# ESP32-S2.net
KiCad netlist of a schematic drawn in Altium Designer
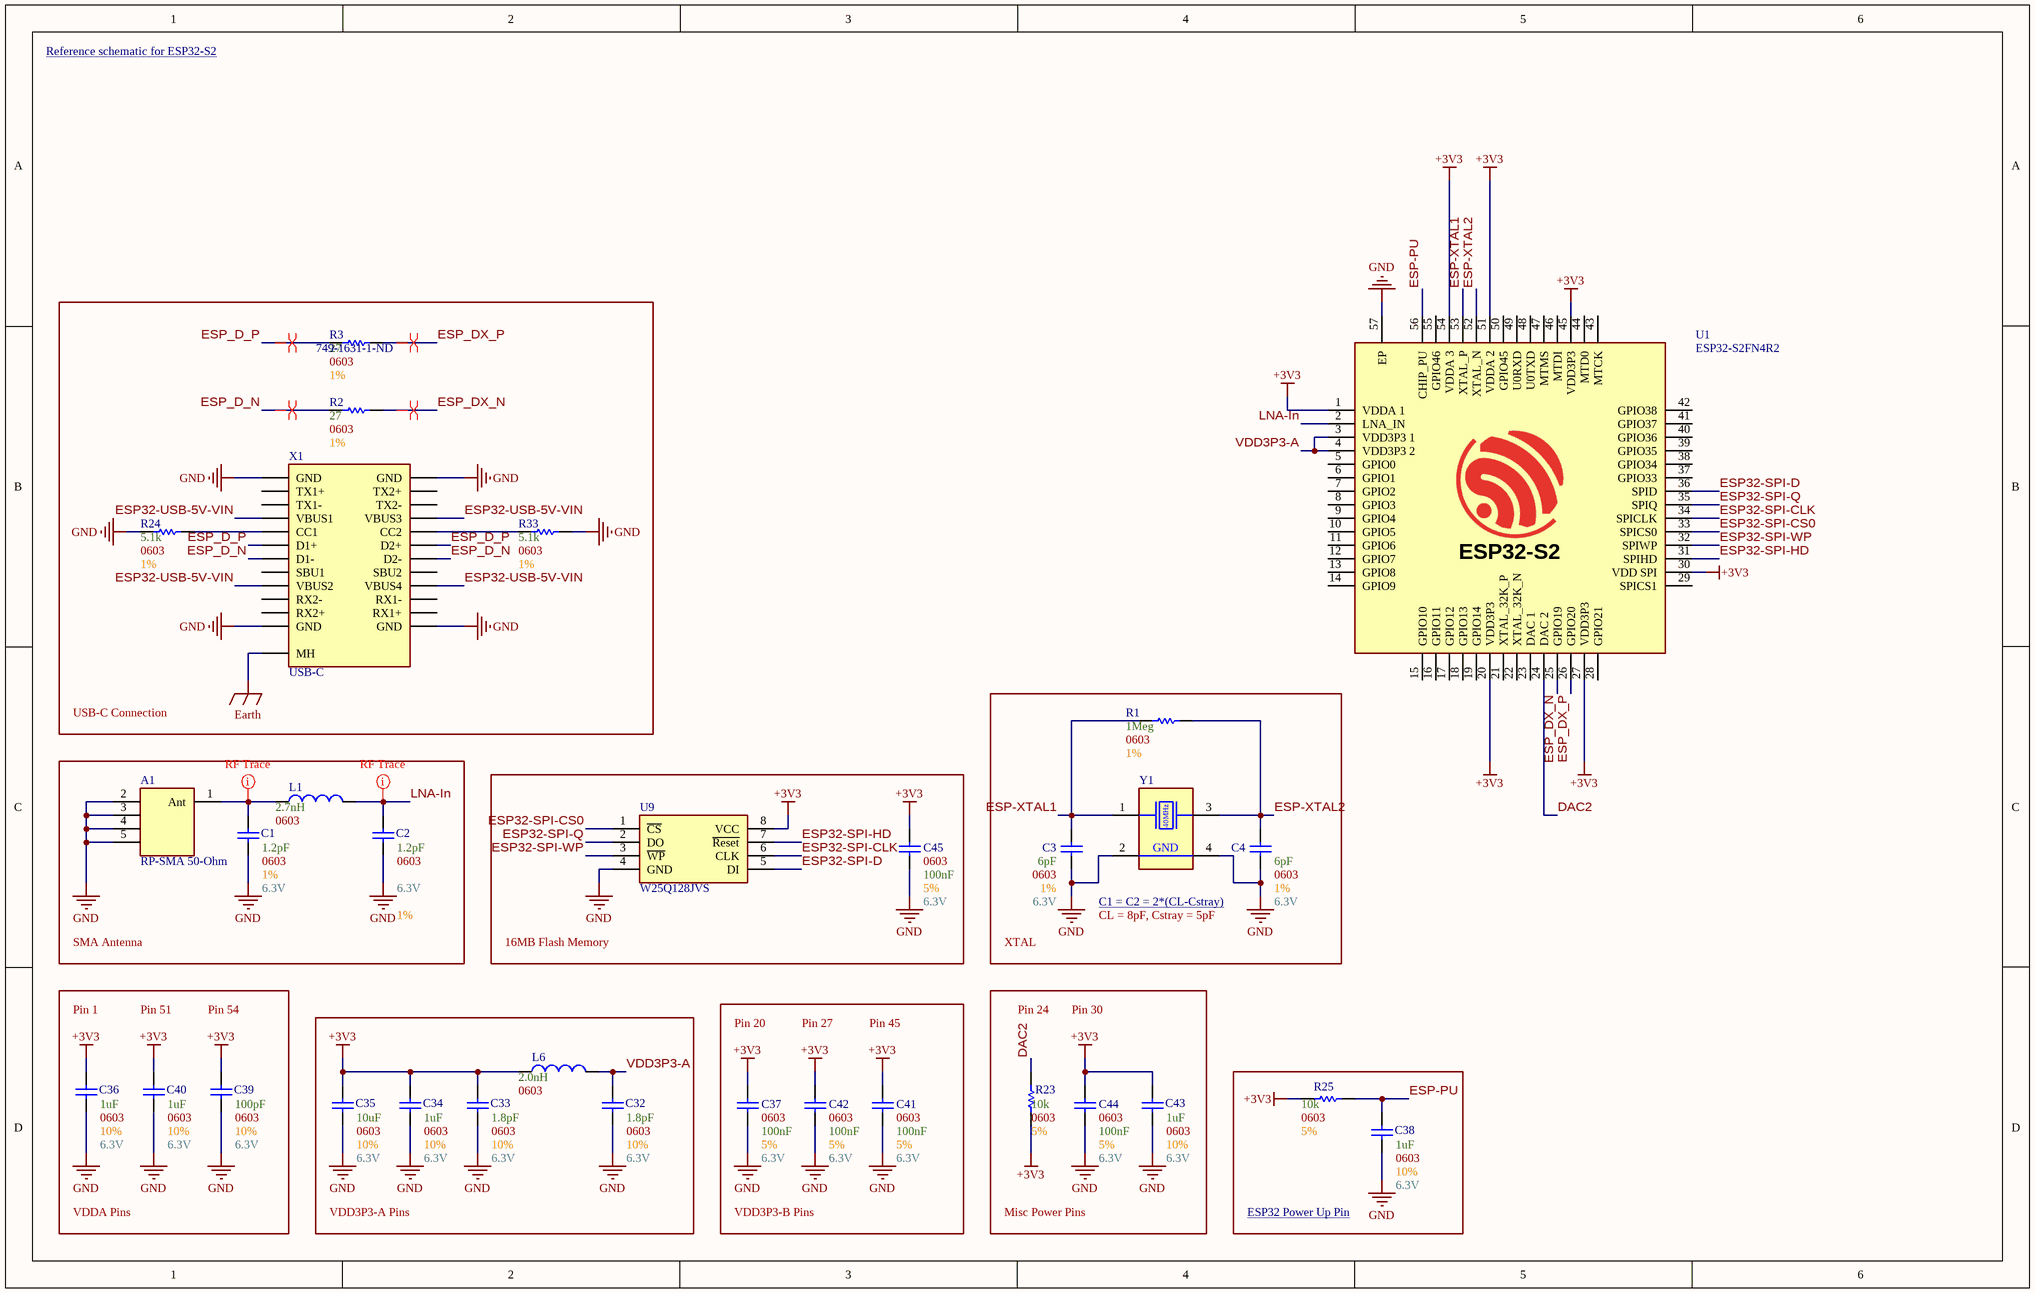
[diagram p0: ESP32-S2.SchDoc]

(export (version "E")
  (design (tool "Eeschema 10.0.6"))
  (components
    (comp (ref "A1")
      (value "RP-SMA 50-Ohm")
      (footprint "[SMA] RP-SMA 90deg Jack")
      (description "PCB.RPSMAFRA.HT")
      (libsource (lib "RADM Connectors") (part "[SMA] RP-SMA 90deg Jack"))
    )
    (comp (ref "C1")
      (value "SMD Nonpolarized")
      (footprint "[Cap] SMD 0603")
      (fields
        (field (name "VOLTAGE") "6.3V")
        (field (name "TOLERANCE") "1%")
        (field (name "SIZE PACKAGE") "0603")
        (field (name "CAPACITANCE") "1.2pF")
      )
      (libsource (lib "RADM Components") (part "[Cap] SMD Nonpolarized"))
    )
    (comp (ref "C2")
      (value "SMD Nonpolarized")
      (footprint "[Cap] SMD 0603")
      (fields
        (field (name "VOLTAGE") "6.3V")
        (field (name "TOLERANCE") "1%")
        (field (name "SIZE PACKAGE") "0603")
        (field (name "CAPACITANCE") "1.2pF")
      )
      (libsource (lib "RADM Components") (part "[Cap] SMD Nonpolarized"))
    )
    (comp (ref "C3")
      (value "SMD Nonpolarized")
      (footprint "[Cap] SMD 0603")
      (fields
        (field (name "VOLTAGE") "6.3V")
        (field (name "TOLERANCE") "1%")
        (field (name "SIZE PACKAGE") "0603")
        (field (name "CAPACITANCE") "6pF")
      )
      (libsource (lib "RADM Components") (part "[Cap] SMD Nonpolarized"))
    )
    (comp (ref "C4")
      (value "SMD Nonpolarized")
      (footprint "[Cap] SMD 0603")
      (fields
        (field (name "VOLTAGE") "6.3V")
        (field (name "TOLERANCE") "1%")
        (field (name "SIZE PACKAGE") "0603")
        (field (name "CAPACITANCE") "6pF")
      )
      (libsource (lib "RADM Components") (part "[Cap] SMD Nonpolarized"))
    )
    (comp (ref "C32")
      (value "SMD Nonpolarized")
      (footprint "[Cap] SMD 0603")
      (fields
        (field (name "VOLTAGE") "6.3V")
        (field (name "TOLERANCE") "10%")
        (field (name "SIZE PACKAGE") "0603")
        (field (name "CAPACITANCE") "1.8pF")
      )
      (libsource (lib "RADM Components") (part "[Cap] SMD Nonpolarized"))
    )
    (comp (ref "C33")
      (value "SMD Nonpolarized")
      (footprint "[Cap] SMD 0603")
      (fields
        (field (name "VOLTAGE") "6.3V")
        (field (name "TOLERANCE") "10%")
        (field (name "SIZE PACKAGE") "0603")
        (field (name "CAPACITANCE") "1.8pF")
      )
      (libsource (lib "RADM Components") (part "[Cap] SMD Nonpolarized"))
    )
    (comp (ref "C34")
      (value "SMD Nonpolarized")
      (footprint "[Cap] SMD 0603")
      (fields
        (field (name "VOLTAGE") "6.3V")
        (field (name "TOLERANCE") "10%")
        (field (name "SIZE PACKAGE") "0603")
        (field (name "CAPACITANCE") "1uF")
      )
      (libsource (lib "RADM Components") (part "[Cap] SMD Nonpolarized"))
    )
    (comp (ref "C35")
      (value "SMD Nonpolarized")
      (footprint "[Cap] SMD 0603")
      (fields
        (field (name "VOLTAGE") "6.3V")
        (field (name "TOLERANCE") "10%")
        (field (name "SIZE PACKAGE") "0603")
        (field (name "CAPACITANCE") "10uF")
      )
      (libsource (lib "RADM Components") (part "[Cap] SMD Nonpolarized"))
    )
    (comp (ref "C36")
      (value "SMD Nonpolarized")
      (footprint "[Cap] SMD 0603")
      (fields
        (field (name "VOLTAGE") "6.3V")
        (field (name "TOLERANCE") "10%")
        (field (name "SIZE PACKAGE") "0603")
        (field (name "CAPACITANCE") "1uF")
      )
      (libsource (lib "RADM Components") (part "[Cap] SMD Nonpolarized"))
    )
    (comp (ref "C37")
      (value "[Cap] SMD Nonpolarized")
      (footprint "[Cap] SMD 0603")
      (fields
        (field (name "SIZE PACKAGE") "0603")
        (field (name "CAPACITANCE") "100nF")
        (field (name "VOLTAGE") "6.3V")
        (field (name "TOLERANCE") "5%")
      )
      (libsource (lib "RADM Components") (part "[Cap] SMD Nonpolarized"))
    )
    (comp (ref "C38")
      (value "SMD Nonpolarized")
      (footprint "[Cap] SMD 0603")
      (fields
        (field (name "VOLTAGE") "6.3V")
        (field (name "TOLERANCE") "10%")
        (field (name "SIZE PACKAGE") "0603")
        (field (name "CAPACITANCE") "1uF")
      )
      (libsource (lib "RADM Components") (part "[Cap] SMD Nonpolarized"))
    )
    (comp (ref "C39")
      (value "SMD Nonpolarized")
      (footprint "[Cap] SMD 0603")
      (fields
        (field (name "VOLTAGE") "6.3V")
        (field (name "TOLERANCE") "10%")
        (field (name "SIZE PACKAGE") "0603")
        (field (name "CAPACITANCE") "100pF")
      )
      (libsource (lib "RADM Components") (part "[Cap] SMD Nonpolarized"))
    )
    (comp (ref "C40")
      (value "SMD Nonpolarized")
      (footprint "[Cap] SMD 0603")
      (fields
        (field (name "VOLTAGE") "6.3V")
        (field (name "TOLERANCE") "10%")
        (field (name "SIZE PACKAGE") "0603")
        (field (name "CAPACITANCE") "1uF")
      )
      (libsource (lib "RADM Components") (part "[Cap] SMD Nonpolarized"))
    )
    (comp (ref "C41")
      (value "[Cap] SMD Nonpolarized")
      (footprint "[Cap] SMD 0603")
      (fields
        (field (name "SIZE PACKAGE") "0603")
        (field (name "CAPACITANCE") "100nF")
        (field (name "VOLTAGE") "6.3V")
        (field (name "TOLERANCE") "5%")
      )
      (libsource (lib "RADM Components") (part "[Cap] SMD Nonpolarized"))
    )
    (comp (ref "C42")
      (value "[Cap] SMD Nonpolarized")
      (footprint "[Cap] SMD 0603")
      (fields
        (field (name "SIZE PACKAGE") "0603")
        (field (name "CAPACITANCE") "100nF")
        (field (name "VOLTAGE") "6.3V")
        (field (name "TOLERANCE") "5%")
      )
      (libsource (lib "RADM Components") (part "[Cap] SMD Nonpolarized"))
    )
    (comp (ref "C43")
      (value "SMD Nonpolarized")
      (footprint "[Cap] SMD 0603")
      (fields
        (field (name "VOLTAGE") "6.3V")
        (field (name "TOLERANCE") "10%")
        (field (name "SIZE PACKAGE") "0603")
        (field (name "CAPACITANCE") "1uF")
      )
      (libsource (lib "RADM Components") (part "[Cap] SMD Nonpolarized"))
    )
    (comp (ref "C44")
      (value "[Cap] SMD Nonpolarized")
      (footprint "[Cap] SMD 0603")
      (fields
        (field (name "SIZE PACKAGE") "0603")
        (field (name "CAPACITANCE") "100nF")
        (field (name "VOLTAGE") "6.3V")
        (field (name "TOLERANCE") "5%")
      )
      (libsource (lib "RADM Components") (part "[Cap] SMD Nonpolarized"))
    )
    (comp (ref "C45")
      (value "[Cap] SMD Nonpolarized")
      (footprint "[Cap] SMD 0603")
      (fields
        (field (name "SIZE PACKAGE") "0603")
        (field (name "CAPACITANCE") "100nF")
        (field (name "VOLTAGE") "6.3V")
        (field (name "TOLERANCE") "5%")
      )
      (libsource (lib "RADM Components") (part "[Cap] SMD Nonpolarized"))
    )
    (comp (ref "L1")
      (value "SMD Inductor")
      (footprint "[Inductor] SMD 0603")
      (fields (field (name "SIZE PACKAGE") "0603") (field (name "INDUCTANCE") "2.7nH"))
      (libsource (lib "RADM Components") (part "[Inductor] SMD Inductor"))
    )
    (comp (ref "L6")
      (value "SMD Inductor")
      (footprint "[Inductor] SMD 0603")
      (fields (field (name "SIZE PACKAGE") "0603") (field (name "INDUCTANCE") "2.0nH"))
      (libsource (lib "RADM Components") (part "[Inductor] SMD Inductor"))
    )
    (comp (ref "R1")
      (value "[Res] SMD Resistor")
      (footprint "[Res] SMD 0603")
      (description "Generic")
      (fields
        (field (name "TOLERANCE") "1%")
        (field (name "RESISTANCE") "1Meg")
        (field (name "SIZE PACKAGE") "0603")
      )
      (libsource (lib "RADM Components") (part "[Res] SMD Resistor"))
    )
    (comp (ref "R2")
      (value "[Res] SMD Resistor")
      (footprint "[Res] SMD 0603")
      (description "Generic")
      (fields
        (field (name "TOLERANCE") "1%")
        (field (name "RESISTANCE") "27")
        (field (name "SIZE PACKAGE") "0603")
      )
      (libsource (lib "RADM Components") (part "[Res] SMD Resistor"))
    )
    (comp (ref "R3")
      (value "[Res] SMD Resistor")
      (footprint "[Res] SMD 0603")
      (description "Generic")
      (fields
        (field (name "TOLERANCE") "1%")
        (field (name "RESISTANCE") "27")
        (field (name "SIZE PACKAGE") "0603")
        (field (name "SUPPLIER PART NUMBER 1") "749-1631-1-ND")
      )
      (libsource (lib "RADM Components") (part "[Res] SMD Resistor"))
    )
    (comp (ref "R23")
      (value "[Res] SMD Resistor")
      (footprint "[Res] SMD 0603")
      (description "Generic")
      (fields
        (field (name "TOLERANCE") "5%")
        (field (name "RESISTANCE") "10k")
        (field (name "SIZE PACKAGE") "0603")
      )
      (libsource (lib "RADM Components") (part "[Res] SMD Resistor"))
    )
    (comp (ref "R24")
      (value "[Res] SMD Resistor")
      (footprint "[Res] SMD 0603")
      (description "Generic")
      (fields
        (field (name "TOLERANCE") "1%")
        (field (name "RESISTANCE") "5.1k")
        (field (name "SIZE PACKAGE") "0603")
      )
      (libsource (lib "RADM Components") (part "[Res] SMD Resistor"))
    )
    (comp (ref "R25")
      (value "[Res] SMD Resistor")
      (footprint "[Res] SMD 0603")
      (description "Generic")
      (fields
        (field (name "TOLERANCE") "5%")
        (field (name "RESISTANCE") "10k")
        (field (name "SIZE PACKAGE") "0603")
      )
      (libsource (lib "RADM Components") (part "[Res] SMD Resistor"))
    )
    (comp (ref "R33")
      (value "[Res] SMD Resistor")
      (footprint "[Res] SMD 0603")
      (description "Generic")
      (fields
        (field (name "TOLERANCE") "1%")
        (field (name "RESISTANCE") "5.1k")
        (field (name "SIZE PACKAGE") "0603")
      )
      (libsource (lib "RADM Components") (part "[Res] SMD Resistor"))
    )
    (comp (ref "U1")
      (value "ESP32-S2FN4R2")
      (footprint "[MCU] ESP32-S2")
      (libsource (lib "RADM Components") (part "[MCU] ESP32-S2"))
    )
    (comp (ref "U9")
      (value "W25Q128JVS")
      (footprint "[Mem] 16Mb Flash Memory")
      (description "W25Q128JVSIQ TR")
      (libsource (lib "RADM Components") (part "[Mem] 16Mb Flash Memory"))
    )
    (comp (ref "X1")
      (value "USB-C")
      (footprint "[Port] USB-C")
      (libsource (lib "RADM Connectors") (part "[Port] USB Type-C"))
    )
    (comp (ref "Y1")
      (value "40MHz Crystal")
      (footprint "[XTAL] SMD 40MHz")
      (description "CX2016DB40000D0FLJCC")
      (libsource (lib "RADM Components") (part "[XTAL] SMD 40MHz"))
    )
  )
  (nets
    (net (code "1") (name "+3V3") (class "Default")
      (node (ref "C33") (pin "2") (pinfunction "2_2") (pintype "passive"))
      (node (ref "C34") (pin "2") (pinfunction "2_2") (pintype "passive"))
      (node (ref "C35") (pin "2") (pinfunction "2_2") (pintype "passive"))
      (node (ref "C36") (pin "2") (pinfunction "2_2") (pintype "passive"))
      (node (ref "C37") (pin "2") (pinfunction "2_2") (pintype "passive"))
      (node (ref "C39") (pin "2") (pinfunction "2_2") (pintype "passive"))
      (node (ref "C40") (pin "2") (pinfunction "2_2") (pintype "passive"))
      (node (ref "C41") (pin "2") (pinfunction "2_2") (pintype "passive"))
      (node (ref "C42") (pin "2") (pinfunction "2_2") (pintype "passive"))
      (node (ref "C43") (pin "2") (pinfunction "2_2") (pintype "passive"))
      (node (ref "C44") (pin "2") (pinfunction "2_2") (pintype "passive"))
      (node (ref "C45") (pin "2") (pinfunction "2_2") (pintype "passive"))
      (node (ref "L6") (pin "1") (pinfunction "1_1") (pintype "passive"))
      (node (ref "R23") (pin "1") (pinfunction "1_1") (pintype "passive"))
      (node (ref "R25") (pin "1") (pinfunction "1_1") (pintype "passive"))
      (node (ref "U1") (pin "1") (pinfunction "VDDA_1_1") (pintype "passive"))
      (node (ref "U1") (pin "20") (pinfunction "VDD3P3_20") (pintype "passive"))
      (node (ref "U1") (pin "27") (pinfunction "VDD3P3_27") (pintype "passive"))
      (node (ref "U1") (pin "30") (pinfunction "VDD_SPI_30") (pintype "passive"))
      (node (ref "U1") (pin "45") (pinfunction "VDD3P3_45") (pintype "passive"))
      (node (ref "U1") (pin "51") (pinfunction "VDDA_2_51") (pintype "passive"))
      (node (ref "U1") (pin "54") (pinfunction "VDDA_3_54") (pintype "passive"))
      (node (ref "U9") (pin "8") (pinfunction "VCC_8") (pintype "passive"))
    )
    (net (code "2") (name "/DAC2") (class "Default")
      (node (ref "R23") (pin "2") (pinfunction "2_2") (pintype "passive"))
      (node (ref "U1") (pin "24") (pinfunction "DAC_2_24") (pintype "passive"))
    )
    (net (code "3") (name "/ESP-PU") (class "Default")
      (node (ref "C38") (pin "2") (pinfunction "2_2") (pintype "passive"))
      (node (ref "R25") (pin "2") (pinfunction "2_2") (pintype "passive"))
      (node (ref "U1") (pin "56") (pinfunction "CHIP_PU_56") (pintype "passive"))
    )
    (net (code "4") (name "/ESP-XTAL1") (class "Default")
      (node (ref "C3") (pin "2") (pinfunction "2_2") (pintype "passive"))
      (node (ref "R1") (pin "2") (pinfunction "2_2") (pintype "passive"))
      (node (ref "U1") (pin "53") (pinfunction "XTAL_P_53") (pintype "passive"))
      (node (ref "Y1") (pin "1") (pinfunction "XTAL1_1") (pintype "power_in"))
    )
    (net (code "5") (name "/ESP-XTAL2") (class "Default")
      (node (ref "C4") (pin "2") (pinfunction "2_2") (pintype "passive"))
      (node (ref "R1") (pin "1") (pinfunction "1_1") (pintype "passive"))
      (node (ref "U1") (pin "52") (pinfunction "XTAL_N_52") (pintype "passive"))
      (node (ref "Y1") (pin "3") (pinfunction "XTAL2_3") (pintype "power_in"))
    )
    (net (code "6") (name "/ESP32-SPI-CLK") (class "Default")
      (node (ref "U1") (pin "34") (pinfunction "SPICLK_34") (pintype "passive"))
      (node (ref "U9") (pin "6") (pinfunction "CLK_6") (pintype "passive"))
    )
    (net (code "7") (name "/ESP32-SPI-CS0") (class "Default")
      (node (ref "U1") (pin "33") (pinfunction "SPICS0_33") (pintype "passive"))
      (node (ref "U9") (pin "1") (pinfunction "~{CS}_1") (pintype "passive"))
    )
    (net (code "8") (name "/ESP32-SPI-D") (class "Default")
      (node (ref "U1") (pin "36") (pinfunction "SPID_36") (pintype "passive"))
      (node (ref "U9") (pin "5") (pinfunction "DI_5") (pintype "passive"))
    )
    (net (code "9") (name "/ESP32-SPI-HD") (class "Default")
      (node (ref "U1") (pin "31") (pinfunction "SPIHD_31") (pintype "passive"))
      (node (ref "U9") (pin "7") (pinfunction "~{Reset}_7") (pintype "passive"))
    )
    (net (code "10") (name "/ESP32-SPI-Q") (class "Default")
      (node (ref "U1") (pin "35") (pinfunction "SPIQ_35") (pintype "passive"))
      (node (ref "U9") (pin "2") (pinfunction "DO_2") (pintype "passive"))
    )
    (net (code "11") (name "/ESP32-SPI-WP") (class "Default")
      (node (ref "U1") (pin "32") (pinfunction "SPIWP_32") (pintype "passive"))
      (node (ref "U9") (pin "3") (pinfunction "~{WP}_3") (pintype "passive"))
    )
    (net (code "12") (name "/ESP32-USB-5V-VIN") (class "Default")
      (node (ref "X1") (pin "A4") (pinfunction "VBUS1_A4") (pintype "passive"))
      (node (ref "X1") (pin "A9") (pinfunction "VBUS2_A9") (pintype "passive"))
      (node (ref "X1") (pin "B4") (pinfunction "VBUS3_B4") (pintype "passive"))
      (node (ref "X1") (pin "B9") (pinfunction "VBUS4_B9") (pintype "passive"))
    )
    (net (code "13") (name "/ESP_DX_N") (class "Default")
      (node (ref "R2") (pin "2") (pinfunction "2_2") (pintype "passive"))
      (node (ref "U1") (pin "25") (pinfunction "GPIO19_25") (pintype "passive"))
    )
    (net (code "14") (name "/ESP_DX_P") (class "Default")
      (node (ref "R3") (pin "2") (pinfunction "2_2") (pintype "passive"))
      (node (ref "U1") (pin "26") (pinfunction "GPIO20_26") (pintype "passive"))
    )
    (net (code "15") (name "/ESP_D_N") (class "Default")
      (node (ref "R2") (pin "1") (pinfunction "1_1") (pintype "passive"))
      (node (ref "X1") (pin "A7") (pinfunction "D1-_A7") (pintype "passive"))
      (node (ref "X1") (pin "B7") (pinfunction "D2-_B7") (pintype "passive"))
    )
    (net (code "16") (name "/ESP_D_P") (class "Default")
      (node (ref "R3") (pin "1") (pinfunction "1_1") (pintype "passive"))
      (node (ref "X1") (pin "A6") (pinfunction "D1+_A6") (pintype "passive"))
      (node (ref "X1") (pin "B6") (pinfunction "D2+_B6") (pintype "passive"))
    )
    (net (code "17") (name "/LNA-In") (class "Default")
      (node (ref "C2") (pin "2") (pinfunction "2_2") (pintype "passive"))
      (node (ref "L1") (pin "2") (pinfunction "2_2") (pintype "passive"))
      (node (ref "U1") (pin "2") (pinfunction "LNA_IN_2") (pintype "passive"))
    )
    (net (code "18") (name "/VDD3P3-A") (class "Default")
      (node (ref "C32") (pin "2") (pinfunction "2_2") (pintype "passive"))
      (node (ref "L6") (pin "2") (pinfunction "2_2") (pintype "passive"))
      (node (ref "U1") (pin "3") (pinfunction "VDD3P3_1_3") (pintype "passive"))
      (node (ref "U1") (pin "4") (pinfunction "VDD3P3_2_4") (pintype "passive"))
    )
    (net (code "19") (name "Earth") (class "Default")
      (node (ref "X1") (pin "MH") (pinfunction "MH_MH") (pintype "passive"))
    )
    (net (code "20") (name "GND") (class "Default")
      (node (ref "A1") (pin "2") (pinfunction "2_2") (pintype "passive"))
      (node (ref "A1") (pin "3") (pinfunction "3_3") (pintype "passive"))
      (node (ref "A1") (pin "4") (pinfunction "4_4") (pintype "passive"))
      (node (ref "A1") (pin "5") (pinfunction "5_5") (pintype "passive"))
      (node (ref "C1") (pin "1") (pinfunction "1_1") (pintype "passive"))
      (node (ref "C2") (pin "1") (pinfunction "1_1") (pintype "passive"))
      (node (ref "C3") (pin "1") (pinfunction "1_1") (pintype "passive"))
      (node (ref "C32") (pin "1") (pinfunction "1_1") (pintype "passive"))
      (node (ref "C33") (pin "1") (pinfunction "1_1") (pintype "passive"))
      (node (ref "C34") (pin "1") (pinfunction "1_1") (pintype "passive"))
      (node (ref "C35") (pin "1") (pinfunction "1_1") (pintype "passive"))
      (node (ref "C36") (pin "1") (pinfunction "1_1") (pintype "passive"))
      (node (ref "C37") (pin "1") (pinfunction "1_1") (pintype "passive"))
      (node (ref "C38") (pin "1") (pinfunction "1_1") (pintype "passive"))
      (node (ref "C39") (pin "1") (pinfunction "1_1") (pintype "passive"))
      (node (ref "C4") (pin "1") (pinfunction "1_1") (pintype "passive"))
      (node (ref "C40") (pin "1") (pinfunction "1_1") (pintype "passive"))
      (node (ref "C41") (pin "1") (pinfunction "1_1") (pintype "passive"))
      (node (ref "C42") (pin "1") (pinfunction "1_1") (pintype "passive"))
      (node (ref "C43") (pin "1") (pinfunction "1_1") (pintype "passive"))
      (node (ref "C44") (pin "1") (pinfunction "1_1") (pintype "passive"))
      (node (ref "C45") (pin "1") (pinfunction "1_1") (pintype "passive"))
      (node (ref "R24") (pin "1") (pinfunction "1_1") (pintype "passive"))
      (node (ref "R33") (pin "2") (pinfunction "2_2") (pintype "passive"))
      (node (ref "U1") (pin "57") (pinfunction "EP_57") (pintype "passive"))
      (node (ref "U9") (pin "4") (pinfunction "GND_4") (pintype "passive"))
      (node (ref "X1") (pin "A1") (pinfunction "GND_A1") (pintype "passive"))
      (node (ref "X1") (pin "A12") (pinfunction "GND_A12") (pintype "passive"))
      (node (ref "X1") (pin "B1") (pinfunction "GND_B1") (pintype "passive"))
      (node (ref "X1") (pin "B12") (pinfunction "GND_B12") (pintype "passive"))
      (node (ref "Y1") (pin "2") (pinfunction "GND_2") (pintype "power_in"))
      (node (ref "Y1") (pin "4") (pinfunction "GND_4") (pintype "power_in"))
    )
    (net (code "21") (name "Net-(A1-Ant)") (class "Default")
      (node (ref "A1") (pin "1") (pinfunction "Ant_1") (pintype "passive"))
      (node (ref "C1") (pin "2") (pinfunction "2_2") (pintype "passive"))
      (node (ref "L1") (pin "1") (pinfunction "1_1") (pintype "passive"))
    )
    (net (code "22") (name "Net-(X1-CC1)") (class "Default")
      (node (ref "R24") (pin "2") (pinfunction "2_2") (pintype "passive"))
      (node (ref "X1") (pin "A5") (pinfunction "CC1_A5") (pintype "passive"))
    )
    (net (code "23") (name "Net-(X1-CC2)") (class "Default")
      (node (ref "R33") (pin "1") (pinfunction "1_1") (pintype "passive"))
      (node (ref "X1") (pin "B5") (pinfunction "CC2_B5") (pintype "passive"))
    )
    (net (code "24") (name "unconnected-(U1-DAC_1-Pad23)") (class "Default")
      (node (ref "U1") (pin "23") (pinfunction "DAC_1_23") (pintype "passive"))
    )
    (net (code "25") (name "unconnected-(U1-GPIO0-Pad5)") (class "Default")
      (node (ref "U1") (pin "5") (pinfunction "GPIO0_5") (pintype "passive"))
    )
    (net (code "26") (name "unconnected-(U1-GPIO1-Pad6)") (class "Default")
      (node (ref "U1") (pin "6") (pinfunction "GPIO1_6") (pintype "passive"))
    )
    (net (code "27") (name "unconnected-(U1-GPIO2-Pad7)") (class "Default")
      (node (ref "U1") (pin "7") (pinfunction "GPIO2_7") (pintype "passive"))
    )
    (net (code "28") (name "unconnected-(U1-GPIO3-Pad8)") (class "Default")
      (node (ref "U1") (pin "8") (pinfunction "GPIO3_8") (pintype "passive"))
    )
    (net (code "29") (name "unconnected-(U1-GPIO4-Pad9)") (class "Default")
      (node (ref "U1") (pin "9") (pinfunction "GPIO4_9") (pintype "passive"))
    )
    (net (code "30") (name "unconnected-(U1-GPIO5-Pad10)") (class "Default")
      (node (ref "U1") (pin "10") (pinfunction "GPIO5_10") (pintype "passive"))
    )
    (net (code "31") (name "unconnected-(U1-GPIO6-Pad11)") (class "Default")
      (node (ref "U1") (pin "11") (pinfunction "GPIO6_11") (pintype "passive"))
    )
    (net (code "32") (name "unconnected-(U1-GPIO7-Pad12)") (class "Default")
      (node (ref "U1") (pin "12") (pinfunction "GPIO7_12") (pintype "passive"))
    )
    (net (code "33") (name "unconnected-(U1-GPIO8-Pad13)") (class "Default")
      (node (ref "U1") (pin "13") (pinfunction "GPIO8_13") (pintype "passive"))
    )
    (net (code "34") (name "unconnected-(U1-GPIO9-Pad14)") (class "Default")
      (node (ref "U1") (pin "14") (pinfunction "GPIO9_14") (pintype "passive"))
    )
    (net (code "35") (name "unconnected-(U1-GPIO10-Pad15)") (class "Default")
      (node (ref "U1") (pin "15") (pinfunction "GPIO10_15") (pintype "passive"))
    )
    (net (code "36") (name "unconnected-(U1-GPIO11-Pad16)") (class "Default")
      (node (ref "U1") (pin "16") (pinfunction "GPIO11_16") (pintype "passive"))
    )
    (net (code "37") (name "unconnected-(U1-GPIO12-Pad17)") (class "Default")
      (node (ref "U1") (pin "17") (pinfunction "GPIO12_17") (pintype "passive"))
    )
    (net (code "38") (name "unconnected-(U1-GPIO13-Pad18)") (class "Default")
      (node (ref "U1") (pin "18") (pinfunction "GPIO13_18") (pintype "passive"))
    )
    (net (code "39") (name "unconnected-(U1-GPIO14-Pad19)") (class "Default")
      (node (ref "U1") (pin "19") (pinfunction "GPIO14_19") (pintype "passive"))
    )
    (net (code "40") (name "unconnected-(U1-GPIO21-Pad28)") (class "Default")
      (node (ref "U1") (pin "28") (pinfunction "GPIO21_28") (pintype "passive"))
    )
    (net (code "41") (name "unconnected-(U1-GPIO33-Pad37)") (class "Default")
      (node (ref "U1") (pin "37") (pinfunction "GPIO33_37") (pintype "passive"))
    )
    (net (code "42") (name "unconnected-(U1-GPIO34-Pad38)") (class "Default")
      (node (ref "U1") (pin "38") (pinfunction "GPIO34_38") (pintype "passive"))
    )
    (net (code "43") (name "unconnected-(U1-GPIO35-Pad39)") (class "Default")
      (node (ref "U1") (pin "39") (pinfunction "GPIO35_39") (pintype "passive"))
    )
    (net (code "44") (name "unconnected-(U1-GPIO36-Pad40)") (class "Default")
      (node (ref "U1") (pin "40") (pinfunction "GPIO36_40") (pintype "passive"))
    )
    (net (code "45") (name "unconnected-(U1-GPIO37-Pad41)") (class "Default")
      (node (ref "U1") (pin "41") (pinfunction "GPIO37_41") (pintype "passive"))
    )
    (net (code "46") (name "unconnected-(U1-GPIO38-Pad42)") (class "Default")
      (node (ref "U1") (pin "42") (pinfunction "GPIO38_42") (pintype "passive"))
    )
    (net (code "47") (name "unconnected-(U1-GPIO45-Pad50)") (class "Default")
      (node (ref "U1") (pin "50") (pinfunction "GPIO45_50") (pintype "passive"))
    )
    (net (code "48") (name "unconnected-(U1-GPIO46-Pad55)") (class "Default")
      (node (ref "U1") (pin "55") (pinfunction "GPIO46_55") (pintype "passive"))
    )
    (net (code "49") (name "unconnected-(U1-MTCK-Pad43)") (class "Default")
      (node (ref "U1") (pin "43") (pinfunction "MTCK_43") (pintype "passive"))
    )
    (net (code "50") (name "unconnected-(U1-MTD0-Pad44)") (class "Default")
      (node (ref "U1") (pin "44") (pinfunction "MTD0_44") (pintype "passive"))
    )
    (net (code "51") (name "unconnected-(U1-MTDI-Pad46)") (class "Default")
      (node (ref "U1") (pin "46") (pinfunction "MTDI_46") (pintype "passive"))
    )
    (net (code "52") (name "unconnected-(U1-MTMS-Pad47)") (class "Default")
      (node (ref "U1") (pin "47") (pinfunction "MTMS_47") (pintype "passive"))
    )
    (net (code "53") (name "unconnected-(U1-SPICS1-Pad29)") (class "Default")
      (node (ref "U1") (pin "29") (pinfunction "SPICS1_29") (pintype "passive"))
    )
    (net (code "54") (name "unconnected-(U1-U0RXD-Pad49)") (class "Default")
      (node (ref "U1") (pin "49") (pinfunction "U0RXD_49") (pintype "passive"))
    )
    (net (code "55") (name "unconnected-(U1-U0TXD-Pad48)") (class "Default")
      (node (ref "U1") (pin "48") (pinfunction "U0TXD_48") (pintype "passive"))
    )
    (net (code "56") (name "unconnected-(U1-XTAL_32K_N-Pad22)") (class "Default")
      (node (ref "U1") (pin "22") (pinfunction "XTAL_32K_N_22") (pintype "passive"))
    )
    (net (code "57") (name "unconnected-(U1-XTAL_32K_P-Pad21)") (class "Default")
      (node (ref "U1") (pin "21") (pinfunction "XTAL_32K_P_21") (pintype "passive"))
    )
    (net (code "58") (name "unconnected-(X1-RX1+-PadB11)") (class "Default")
      (node (ref "X1") (pin "B11") (pinfunction "RX1+_B11") (pintype "passive"))
    )
    (net (code "59") (name "unconnected-(X1-RX1--PadB10)") (class "Default")
      (node (ref "X1") (pin "B10") (pinfunction "RX1-_B10") (pintype "passive"))
    )
    (net (code "60") (name "unconnected-(X1-RX2+-PadA11)") (class "Default")
      (node (ref "X1") (pin "A11") (pinfunction "RX2+_A11") (pintype "passive"))
    )
    (net (code "61") (name "unconnected-(X1-RX2--PadA10)") (class "Default")
      (node (ref "X1") (pin "A10") (pinfunction "RX2-_A10") (pintype "passive"))
    )
    (net (code "62") (name "unconnected-(X1-SBU1-PadA8)") (class "Default")
      (node (ref "X1") (pin "A8") (pinfunction "SBU1_A8") (pintype "passive"))
    )
    (net (code "63") (name "unconnected-(X1-SBU2-PadB8)") (class "Default")
      (node (ref "X1") (pin "B8") (pinfunction "SBU2_B8") (pintype "passive"))
    )
    (net (code "64") (name "unconnected-(X1-TX1+-PadA2)") (class "Default")
      (node (ref "X1") (pin "A2") (pinfunction "TX1+_A2") (pintype "passive"))
    )
    (net (code "65") (name "unconnected-(X1-TX1--PadA3)") (class "Default")
      (node (ref "X1") (pin "A3") (pinfunction "TX1-_A3") (pintype "passive"))
    )
    (net (code "66") (name "unconnected-(X1-TX2+-PadB2)") (class "Default")
      (node (ref "X1") (pin "B2") (pinfunction "TX2+_B2") (pintype "passive"))
    )
    (net (code "67") (name "unconnected-(X1-TX2--PadB3)") (class "Default")
      (node (ref "X1") (pin "B3") (pinfunction "TX2-_B3") (pintype "passive"))
    )
  )
)
